# ASD2202.net
KiCad netlist of a schematic drawn in EAGLE
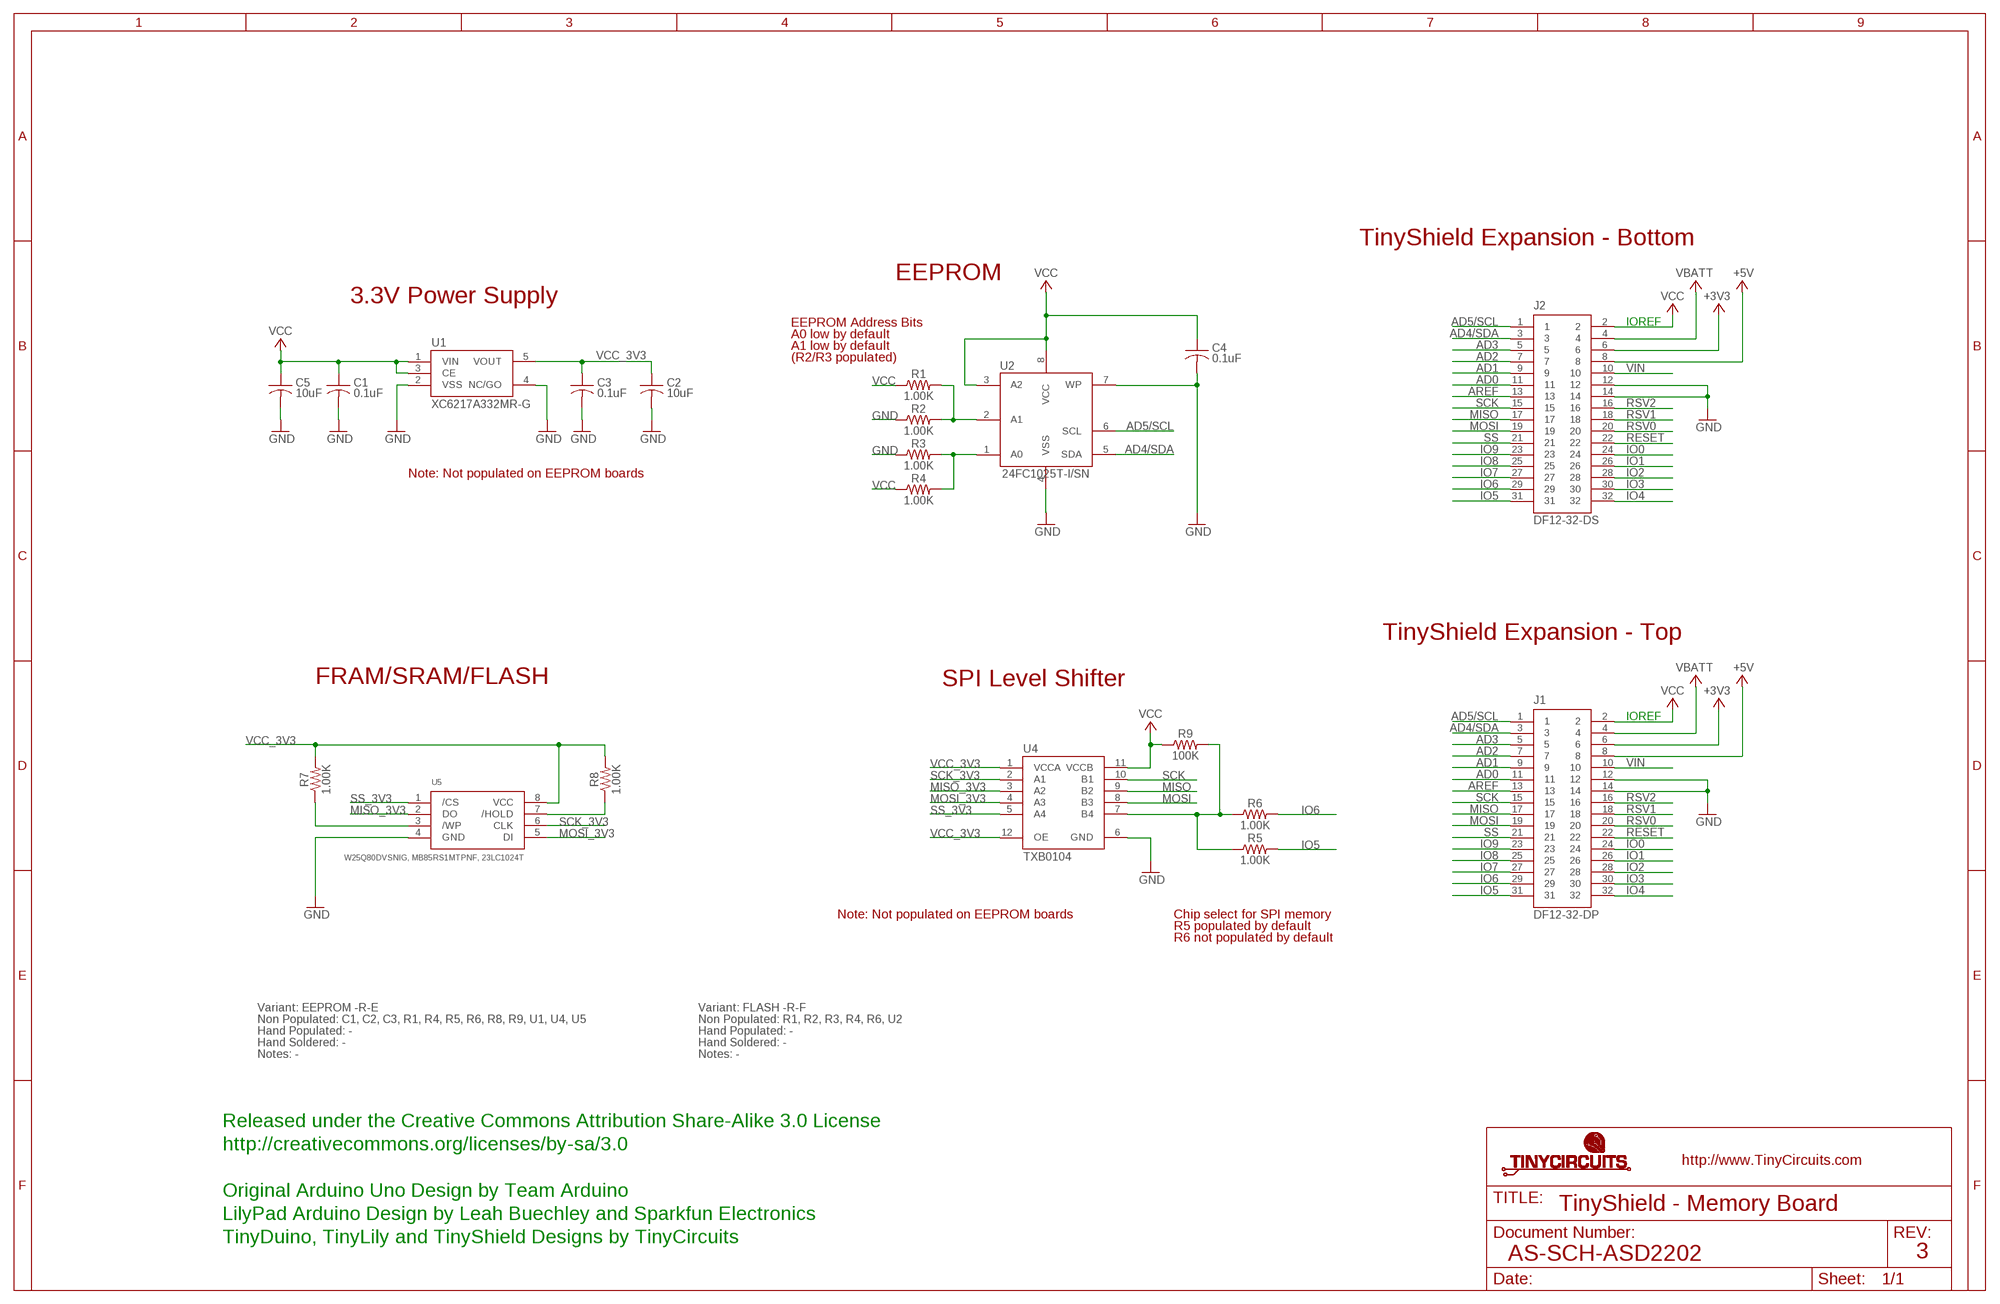
[diagram p0: schematic, sheet 1]

(export (version "E")
  (design (tool "Eeschema 10.0.6"))
  (components
    (comp (ref "C1")
      (value "0.1uF")
      (footprint "eagle-import:C0402")
      (fields (field (name "PARTNO") "AS-ITM-00008") (field (name "PARTNO_1") "AS-ITM-00008"))
      (libsource (lib "eagle-import") (part "AS-ITM-00008"))
    )
    (comp (ref "C2")
      (value "10uF")
      (footprint "eagle-import:C0805")
      (fields (field (name "PARTNO") "AS-ITM-00045") (field (name "PARTNO_1") "AS-ITM-00045"))
      (libsource (lib "eagle-import") (part "AS-ITM-00045"))
    )
    (comp (ref "C3")
      (value "0.1uF")
      (footprint "eagle-import:C0402")
      (fields (field (name "PARTNO") "AS-ITM-00008") (field (name "PARTNO_1") "AS-ITM-00008"))
      (libsource (lib "eagle-import") (part "AS-ITM-00008"))
    )
    (comp (ref "C4")
      (value "0.1uF")
      (footprint "eagle-import:C0402")
      (fields (field (name "PARTNO") "AS-ITM-00008") (field (name "PARTNO_1") "AS-ITM-00008"))
      (libsource (lib "eagle-import") (part "AS-ITM-00008"))
    )
    (comp (ref "C5")
      (value "10uF")
      (footprint "eagle-import:C0805")
      (fields (field (name "PARTNO") "AS-ITM-00045"))
      (libsource (lib "eagle-import") (part "AS-ITM-00045"))
    )
    (comp (ref "J1")
      (value "DF12-32-DP")
      (footprint "eagle-import:DF12-32-DP")
      (fields (field (name "PARTNO") "AS-ITM-00015") (field (name "PARTNO_1") "AS-ITM-00015"))
      (libsource (lib "eagle-import") (part "AS-ITM-00015"))
    )
    (comp (ref "J2")
      (value "DF12-32-DS")
      (footprint "eagle-import:DF12-32-DS")
      (fields (field (name "PARTNO") "AS-ITM-00012") (field (name "PARTNO_1") "AS-ITM-00012"))
      (libsource (lib "eagle-import") (part "AS-ITM-00012"))
    )
    (comp (ref "R1")
      (value "1.00K")
      (footprint "eagle-import:0402")
      (fields (field (name "PARTNO") "AS-ITM-00003") (field (name "PARTNO_1") "AS-ITM-00003"))
      (libsource (lib "eagle-import") (part "AS-ITM-00003"))
    )
    (comp (ref "R2")
      (value "1.00K")
      (footprint "eagle-import:0402")
      (fields (field (name "PARTNO") "AS-ITM-00003") (field (name "PARTNO_1") "AS-ITM-00003"))
      (libsource (lib "eagle-import") (part "AS-ITM-00003"))
    )
    (comp (ref "R3")
      (value "1.00K")
      (footprint "eagle-import:0402")
      (fields (field (name "PARTNO") "AS-ITM-00003") (field (name "PARTNO_1") "AS-ITM-00003"))
      (libsource (lib "eagle-import") (part "AS-ITM-00003"))
    )
    (comp (ref "R4")
      (value "1.00K")
      (footprint "eagle-import:0402")
      (fields (field (name "PARTNO") "AS-ITM-00003") (field (name "PARTNO_1") "AS-ITM-00003"))
      (libsource (lib "eagle-import") (part "AS-ITM-00003"))
    )
    (comp (ref "R5")
      (value "1.00K")
      (footprint "eagle-import:0402")
      (fields (field (name "PARTNO") "AS-ITM-00003") (field (name "PARTNO_1") "AS-ITM-00003"))
      (libsource (lib "eagle-import") (part "AS-ITM-00003"))
    )
    (comp (ref "R6")
      (value "1.00K")
      (footprint "eagle-import:0402")
      (fields (field (name "PARTNO") "AS-ITM-00003") (field (name "PARTNO_1") "AS-ITM-00003"))
      (libsource (lib "eagle-import") (part "AS-ITM-00003"))
    )
    (comp (ref "R7")
      (value "1.00K")
      (footprint "eagle-import:0402")
      (fields (field (name "PARTNO") "AS-ITM-00003"))
      (libsource (lib "eagle-import") (part "AS-ITM-00003"))
    )
    (comp (ref "R8")
      (value "1.00K")
      (footprint "eagle-import:0402")
      (fields (field (name "PARTNO") "AS-ITM-00003"))
      (libsource (lib "eagle-import") (part "AS-ITM-00003"))
    )
    (comp (ref "R9")
      (value "100K")
      (footprint "eagle-import:0402")
      (fields (field (name "PARTNO") "AS-ITM-00004") (field (name "PARTNO_1") "AS-ITM-00004"))
      (libsource (lib "eagle-import") (part "AS-ITM-00004"))
    )
    (comp (ref "U1")
      (value "XC6217A332MR-G")
      (footprint "eagle-import:SOT-25")
      (fields (field (name "PARTNO") "AS-ITM-00249") (field (name "PARTNO_1") "AS-ITM-00249"))
      (libsource (lib "eagle-import") (part "AS-ITM-00249"))
    )
    (comp (ref "U2")
      (value "24FC1025T-I/SN")
      (footprint "eagle-import:8-SOIC-N")
      (fields (field (name "PARTNO") "AS-ITM-00190"))
      (libsource (lib "eagle-import") (part "AS-ITM-00190"))
    )
    (comp (ref "U4")
      (value "TXB0104")
      (footprint "eagle-import:UQFN-12")
      (fields (field (name "PARTNO") "AS-ITM-00048"))
      (libsource (lib "eagle-import") (part "AS-ITM-00048"))
    )
    (comp (ref "U5")
      (value "W25Q80DVSNIG, MB85RS1MTPNF, 23LC1024T")
      (footprint "eagle-import:8-SOIC-N")
      (fields (field (name "PARTNO") "AS-ITM-00238"))
      (libsource (lib "eagle-import") (part "AS-ITM-00238"))
    )
  )
  (nets
    (net (code "1") (name "+3V3") (class "Default")
      (node (ref "J1") (pin "6") (pinfunction "6_6") (pintype "bidirectional"))
      (node (ref "J2") (pin "6") (pinfunction "6_6") (pintype "bidirectional"))
    )
    (net (code "2") (name "+5V") (class "Default")
      (node (ref "J1") (pin "8") (pinfunction "8_8") (pintype "bidirectional"))
      (node (ref "J2") (pin "8") (pinfunction "8_8") (pintype "bidirectional"))
    )
    (net (code "3") (name "/AD0") (class "Default")
      (node (ref "J1") (pin "11") (pinfunction "11_11") (pintype "bidirectional"))
      (node (ref "J2") (pin "11") (pinfunction "11_11") (pintype "bidirectional"))
    )
    (net (code "4") (name "/AD1") (class "Default")
      (node (ref "J1") (pin "9") (pinfunction "9_9") (pintype "bidirectional"))
      (node (ref "J2") (pin "9") (pinfunction "9_9") (pintype "bidirectional"))
    )
    (net (code "5") (name "/AD2") (class "Default")
      (node (ref "J1") (pin "7") (pinfunction "7_7") (pintype "bidirectional"))
      (node (ref "J2") (pin "7") (pinfunction "7_7") (pintype "bidirectional"))
    )
    (net (code "6") (name "/AD3") (class "Default")
      (node (ref "J1") (pin "5") (pinfunction "5_5") (pintype "bidirectional"))
      (node (ref "J2") (pin "5") (pinfunction "5_5") (pintype "bidirectional"))
    )
    (net (code "7") (name "/AD4{slash}SDA") (class "Default")
      (node (ref "J1") (pin "3") (pinfunction "3_3") (pintype "bidirectional"))
      (node (ref "J2") (pin "3") (pinfunction "3_3") (pintype "bidirectional"))
      (node (ref "U2") (pin "5") (pinfunction "SDA_5") (pintype "bidirectional"))
    )
    (net (code "8") (name "/AD5{slash}SCL") (class "Default")
      (node (ref "J1") (pin "1") (pinfunction "1_1") (pintype "bidirectional"))
      (node (ref "J2") (pin "1") (pinfunction "1_1") (pintype "bidirectional"))
      (node (ref "U2") (pin "6") (pinfunction "SCL_6") (pintype "bidirectional"))
    )
    (net (code "9") (name "/AREF") (class "Default")
      (node (ref "J1") (pin "13") (pinfunction "13_13") (pintype "bidirectional"))
      (node (ref "J2") (pin "13") (pinfunction "13_13") (pintype "bidirectional"))
    )
    (net (code "10") (name "/IO0") (class "Default")
      (node (ref "J1") (pin "24") (pinfunction "24_24") (pintype "bidirectional"))
      (node (ref "J2") (pin "24") (pinfunction "24_24") (pintype "bidirectional"))
    )
    (net (code "11") (name "/IO1") (class "Default")
      (node (ref "J1") (pin "26") (pinfunction "26_26") (pintype "bidirectional"))
      (node (ref "J2") (pin "26") (pinfunction "26_26") (pintype "bidirectional"))
    )
    (net (code "12") (name "/IO2") (class "Default")
      (node (ref "J1") (pin "28") (pinfunction "28_28") (pintype "bidirectional"))
      (node (ref "J2") (pin "28") (pinfunction "28_28") (pintype "bidirectional"))
    )
    (net (code "13") (name "/IO3") (class "Default")
      (node (ref "J1") (pin "30") (pinfunction "30_30") (pintype "bidirectional"))
      (node (ref "J2") (pin "30") (pinfunction "30_30") (pintype "bidirectional"))
    )
    (net (code "14") (name "/IO4") (class "Default")
      (node (ref "J1") (pin "32") (pinfunction "32_32") (pintype "bidirectional"))
      (node (ref "J2") (pin "32") (pinfunction "32_32") (pintype "bidirectional"))
    )
    (net (code "15") (name "/IO5") (class "Default")
      (node (ref "J1") (pin "31") (pinfunction "31_31") (pintype "bidirectional"))
      (node (ref "J2") (pin "31") (pinfunction "31_31") (pintype "bidirectional"))
      (node (ref "R5") (pin "2") (pinfunction "2_2") (pintype "passive"))
    )
    (net (code "16") (name "/IO6") (class "Default")
      (node (ref "J1") (pin "29") (pinfunction "29_29") (pintype "bidirectional"))
      (node (ref "J2") (pin "29") (pinfunction "29_29") (pintype "bidirectional"))
      (node (ref "R6") (pin "2") (pinfunction "2_2") (pintype "passive"))
    )
    (net (code "17") (name "/IO7") (class "Default")
      (node (ref "J1") (pin "27") (pinfunction "27_27") (pintype "bidirectional"))
      (node (ref "J2") (pin "27") (pinfunction "27_27") (pintype "bidirectional"))
    )
    (net (code "18") (name "/IO8") (class "Default")
      (node (ref "J1") (pin "25") (pinfunction "25_25") (pintype "bidirectional"))
      (node (ref "J2") (pin "25") (pinfunction "25_25") (pintype "bidirectional"))
    )
    (net (code "19") (name "/IO9") (class "Default")
      (node (ref "J1") (pin "23") (pinfunction "23_23") (pintype "bidirectional"))
      (node (ref "J2") (pin "23") (pinfunction "23_23") (pintype "bidirectional"))
    )
    (net (code "20") (name "/MISO") (class "Default")
      (node (ref "J1") (pin "17") (pinfunction "17_17") (pintype "bidirectional"))
      (node (ref "J2") (pin "17") (pinfunction "17_17") (pintype "bidirectional"))
      (node (ref "U4") (pin "9") (pinfunction "B2_9") (pintype "bidirectional"))
    )
    (net (code "21") (name "/MISO_3V3") (class "Default")
      (node (ref "U4") (pin "3") (pinfunction "A2_3") (pintype "bidirectional"))
      (node (ref "U5") (pin "2") (pinfunction "DO_2") (pintype "bidirectional"))
    )
    (net (code "22") (name "/MOSI") (class "Default")
      (node (ref "J1") (pin "19") (pinfunction "19_19") (pintype "bidirectional"))
      (node (ref "J2") (pin "19") (pinfunction "19_19") (pintype "bidirectional"))
      (node (ref "U4") (pin "8") (pinfunction "B3_8") (pintype "bidirectional"))
    )
    (net (code "23") (name "/MOSI_3V3") (class "Default")
      (node (ref "U4") (pin "4") (pinfunction "A3_4") (pintype "bidirectional"))
      (node (ref "U5") (pin "5") (pinfunction "DI_5") (pintype "bidirectional"))
    )
    (net (code "24") (name "/RESET") (class "Default")
      (node (ref "J1") (pin "22") (pinfunction "22_22") (pintype "bidirectional"))
      (node (ref "J2") (pin "22") (pinfunction "22_22") (pintype "bidirectional"))
    )
    (net (code "25") (name "/RSV0") (class "Default")
      (node (ref "J1") (pin "20") (pinfunction "20_20") (pintype "bidirectional"))
      (node (ref "J2") (pin "20") (pinfunction "20_20") (pintype "bidirectional"))
    )
    (net (code "26") (name "/RSV1") (class "Default")
      (node (ref "J1") (pin "18") (pinfunction "18_18") (pintype "bidirectional"))
      (node (ref "J2") (pin "18") (pinfunction "18_18") (pintype "bidirectional"))
    )
    (net (code "27") (name "/RSV2") (class "Default")
      (node (ref "J1") (pin "16") (pinfunction "16_16") (pintype "bidirectional"))
      (node (ref "J2") (pin "16") (pinfunction "16_16") (pintype "bidirectional"))
    )
    (net (code "28") (name "/SCK") (class "Default")
      (node (ref "J1") (pin "15") (pinfunction "15_15") (pintype "bidirectional"))
      (node (ref "J2") (pin "15") (pinfunction "15_15") (pintype "bidirectional"))
      (node (ref "U4") (pin "10") (pinfunction "B1_10") (pintype "bidirectional"))
    )
    (net (code "29") (name "/SCK_3V3") (class "Default")
      (node (ref "U4") (pin "2") (pinfunction "A1_2") (pintype "bidirectional"))
      (node (ref "U5") (pin "6") (pinfunction "CLK_6") (pintype "bidirectional"))
    )
    (net (code "30") (name "/SS") (class "Default")
      (node (ref "J1") (pin "21") (pinfunction "21_21") (pintype "bidirectional"))
      (node (ref "J2") (pin "21") (pinfunction "21_21") (pintype "bidirectional"))
    )
    (net (code "31") (name "/SS_3V3") (class "Default")
      (node (ref "U4") (pin "5") (pinfunction "A4_5") (pintype "bidirectional"))
      (node (ref "U5") (pin "1") (pinfunction "/CS_1") (pintype "bidirectional"))
    )
    (net (code "32") (name "/VCC_3V3") (class "Default")
      (node (ref "C2") (pin "1") (pinfunction "1_1") (pintype "passive"))
      (node (ref "C3") (pin "1") (pinfunction "1_1") (pintype "passive"))
      (node (ref "R7") (pin "2") (pinfunction "2_2") (pintype "passive"))
      (node (ref "R8") (pin "2") (pinfunction "2_2") (pintype "passive"))
      (node (ref "U1") (pin "5") (pinfunction "VOUT_5") (pintype "bidirectional"))
      (node (ref "U4") (pin "1") (pinfunction "VCCA_1") (pintype "bidirectional"))
      (node (ref "U4") (pin "12") (pinfunction "OE_12") (pintype "bidirectional"))
      (node (ref "U5") (pin "8") (pinfunction "VCC_8") (pintype "bidirectional"))
    )
    (net (code "33") (name "/VIN") (class "Default")
      (node (ref "J1") (pin "10") (pinfunction "10_10") (pintype "bidirectional"))
      (node (ref "J2") (pin "10") (pinfunction "10_10") (pintype "bidirectional"))
    )
    (net (code "34") (name "GND") (class "Default")
      (node (ref "C1") (pin "2") (pinfunction "2_2") (pintype "passive"))
      (node (ref "C2") (pin "2") (pinfunction "2_2") (pintype "passive"))
      (node (ref "C3") (pin "2") (pinfunction "2_2") (pintype "passive"))
      (node (ref "C4") (pin "2") (pinfunction "2_2") (pintype "passive"))
      (node (ref "C5") (pin "2") (pinfunction "2_2") (pintype "passive"))
      (node (ref "J1") (pin "12") (pinfunction "12_12") (pintype "bidirectional"))
      (node (ref "J1") (pin "14") (pinfunction "14_14") (pintype "bidirectional"))
      (node (ref "J2") (pin "12") (pinfunction "12_12") (pintype "bidirectional"))
      (node (ref "J2") (pin "14") (pinfunction "14_14") (pintype "bidirectional"))
      (node (ref "R2") (pin "1") (pinfunction "1_1") (pintype "passive"))
      (node (ref "R3") (pin "1") (pinfunction "1_1") (pintype "passive"))
      (node (ref "U1") (pin "2") (pinfunction "VSS_2") (pintype "power_in"))
      (node (ref "U1") (pin "4") (pinfunction "NC/GO_4") (pintype "bidirectional"))
      (node (ref "U2") (pin "4") (pinfunction "VSS_4") (pintype "bidirectional"))
      (node (ref "U2") (pin "7") (pinfunction "WP_7") (pintype "bidirectional"))
      (node (ref "U4") (pin "6") (pinfunction "GND_6") (pintype "bidirectional"))
      (node (ref "U5") (pin "4") (pinfunction "GND_4") (pintype "bidirectional"))
    )
    (net (code "35") (name "Net-(U2-A0)") (class "Default")
      (node (ref "R3") (pin "2") (pinfunction "2_2") (pintype "passive"))
      (node (ref "R4") (pin "2") (pinfunction "2_2") (pintype "passive"))
      (node (ref "U2") (pin "1") (pinfunction "A0_1") (pintype "bidirectional"))
    )
    (net (code "36") (name "Net-(U2-A1)") (class "Default")
      (node (ref "R1") (pin "2") (pinfunction "2_2") (pintype "passive"))
      (node (ref "R2") (pin "2") (pinfunction "2_2") (pintype "passive"))
      (node (ref "U2") (pin "2") (pinfunction "A1_2") (pintype "bidirectional"))
    )
    (net (code "37") (name "Net-(U4-B4)") (class "Default")
      (node (ref "R5") (pin "1") (pinfunction "1_1") (pintype "passive"))
      (node (ref "R6") (pin "1") (pinfunction "1_1") (pintype "passive"))
      (node (ref "R9") (pin "2") (pinfunction "2_2") (pintype "passive"))
      (node (ref "U4") (pin "7") (pinfunction "B4_7") (pintype "bidirectional"))
    )
    (net (code "38") (name "Net-(U5-{slash}HOLD)") (class "Default")
      (node (ref "R8") (pin "1") (pinfunction "1_1") (pintype "passive"))
      (node (ref "U5") (pin "7") (pinfunction "/HOLD_7") (pintype "bidirectional"))
    )
    (net (code "39") (name "Net-(U5-{slash}WP)") (class "Default")
      (node (ref "R7") (pin "1") (pinfunction "1_1") (pintype "passive"))
      (node (ref "U5") (pin "3") (pinfunction "/WP_3") (pintype "bidirectional"))
    )
    (net (code "40") (name "VBATT") (class "Default")
      (node (ref "J1") (pin "4") (pinfunction "4_4") (pintype "bidirectional"))
      (node (ref "J2") (pin "4") (pinfunction "4_4") (pintype "bidirectional"))
    )
    (net (code "41") (name "VCC") (class "Default")
      (node (ref "C1") (pin "1") (pinfunction "1_1") (pintype "passive"))
      (node (ref "C4") (pin "1") (pinfunction "1_1") (pintype "passive"))
      (node (ref "C5") (pin "1") (pinfunction "1_1") (pintype "passive"))
      (node (ref "J1") (pin "2") (pinfunction "2_2") (pintype "bidirectional"))
      (node (ref "J2") (pin "2") (pinfunction "2_2") (pintype "bidirectional"))
      (node (ref "R1") (pin "1") (pinfunction "1_1") (pintype "passive"))
      (node (ref "R4") (pin "1") (pinfunction "1_1") (pintype "passive"))
      (node (ref "R9") (pin "1") (pinfunction "1_1") (pintype "passive"))
      (node (ref "U1") (pin "1") (pinfunction "VIN_1") (pintype "bidirectional"))
      (node (ref "U1") (pin "3") (pinfunction "CE_3") (pintype "bidirectional"))
      (node (ref "U2") (pin "3") (pinfunction "A2_3") (pintype "bidirectional"))
      (node (ref "U2") (pin "8") (pinfunction "VCC_8") (pintype "bidirectional"))
      (node (ref "U4") (pin "11") (pinfunction "VCCB_11") (pintype "bidirectional"))
    )
  )
)
